# Fri3D_IRA_Power.net
KiCad netlist of a schematic drawn in Altium Designer
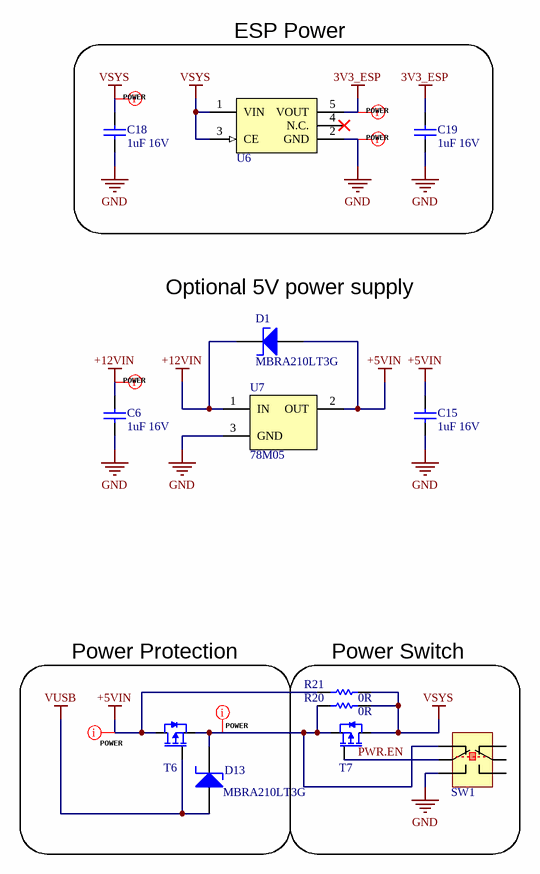
[diagram p0: Fri3D_IRA_Power.SchDoc]

(export (version "E")
  (design (tool "Eeschema 10.0.6"))
  (components
    (comp (ref "C6")
      (value "1uF 16V")
      (footprint "C0603_N")
      (description "Capacitor Ceramic")
      (fields (field (name "Comment") "CAP_CERAMIC"))
      (libsource (lib "Phyx_Components") (part "CAP_CERAMIC"))
    )
    (comp (ref "C15")
      (value "1uF 16V")
      (footprint "C0603_N")
      (description "Capacitor Ceramic")
      (fields (field (name "Comment") "CAP_CERAMIC"))
      (libsource (lib "Phyx_Components") (part "CAP_CERAMIC"))
    )
    (comp (ref "C18")
      (value "1uF 16V")
      (footprint "C0603_N")
      (description "Capacitor Ceramic")
      (fields (field (name "Comment") "CAP_CERAMIC"))
      (libsource (lib "Phyx_Components") (part "CAP_CERAMIC"))
    )
    (comp (ref "C19")
      (value "1uF 16V")
      (footprint "C0603_N")
      (description "Capacitor Ceramic")
      (fields (field (name "Comment") "CAP_CERAMIC"))
      (libsource (lib "Phyx_Components") (part "CAP_CERAMIC"))
    )
    (comp (ref "D1")
      (value "MBRA210LT3G")
      (footprint "SMA_AC")
      (description "=Description")
      (libsource (lib "Phyx_Components") (part "Schottky_AC"))
    )
    (comp (ref "D13")
      (value "MBRA210LT3G")
      (footprint "SMA_AC")
      (description "=Description")
      (libsource (lib "Phyx_Components") (part "Schottky_AC"))
    )
    (comp (ref "R20")
      (value "0R")
      (footprint "R0603_N")
      (fields (field (name "Comment") "RESISTOR"))
      (libsource (lib "Phyx_Components") (part "RESISTOR"))
    )
    (comp (ref "R21")
      (value "0R")
      (footprint "R0603_N")
      (fields (field (name "Comment") "RESISTOR"))
      (libsource (lib "Phyx_Components") (part "RESISTOR"))
    )
    (comp (ref "SW1")
      (value "Mini slide switch 2P2T")
      (footprint "MSS22D18")
      (libsource (lib "Phyx_Components") (part "SW_2P2T"))
    )
    (comp (ref "T6")
      (value "-2.3A -20V P-Ch MOSFET Vgs -1V")
      (footprint "SOT23-3")
      (description "=Description")
      (libsource (lib "Phyx_Components") (part "P_MOSFET_GSD"))
    )
    (comp (ref "T7")
      (value "-2.3A -20V P-Ch MOSFET Vgs -1V")
      (footprint "SOT23-3")
      (description "=Description")
      (libsource (lib "Phyx_Components") (part "P_MOSFET_GSD"))
    )
    (comp (ref "U6")
      (value "3V3 LDO 700mA 50mV")
      (footprint "SOT23-5")
      (description "=Designator")
      (libsource (lib "Phyx_Components") (part "XC6210_SOT"))
    )
    (comp (ref "U7")
      (value "78M05")
      (footprint "TO-252")
      (description "78M05 5V 750mA LDO")
      (libsource (lib "Phyx_Components") (part "78M05"))
    )
  )
  (nets
    (net (code "1") (name "+5VIN") (class "Default")
      (node (ref "C15") (pin "1") (pinfunction "1_1") (pintype "passive"))
      (node (ref "D1") (pin "A") (pinfunction "A_A") (pintype "passive"))
      (node (ref "R21") (pin "2") (pinfunction "2_2") (pintype "passive"))
      (node (ref "T6") (pin "3") (pinfunction "D_3") (pintype "passive"))
      (node (ref "U7") (pin "2") (pinfunction "OUT_2") (pintype "power_in"))
    )
    (net (code "2") (name "+12VIN") (class "Default")
      (node (ref "C6") (pin "1") (pinfunction "1_1") (pintype "passive"))
      (node (ref "D1") (pin "C") (pinfunction "C_C") (pintype "passive"))
      (node (ref "U7") (pin "1") (pinfunction "IN_1") (pintype "power_in"))
    )
    (net (code "3") (name "/PWR.EN") (class "Default")
      (node (ref "SW1") (pin "3") (pinfunction "3_3") (pintype "passive"))
      (node (ref "T7") (pin "1") (pinfunction "G_1") (pintype "passive"))
    )
    (net (code "4") (name "3V3_ESP") (class "Default")
      (node (ref "C19") (pin "1") (pinfunction "1_1") (pintype "passive"))
      (node (ref "U6") (pin "5") (pinfunction "VOUT_5") (pintype "power_in"))
    )
    (net (code "5") (name "GND") (class "Default")
      (node (ref "C15") (pin "2") (pinfunction "2_2") (pintype "passive"))
      (node (ref "C18") (pin "2") (pinfunction "2_2") (pintype "passive"))
      (node (ref "C19") (pin "2") (pinfunction "2_2") (pintype "passive"))
      (node (ref "C6") (pin "2") (pinfunction "2_2") (pintype "passive"))
      (node (ref "SW1") (pin "5") (pinfunction "5_5") (pintype "passive"))
      (node (ref "U6") (pin "2") (pinfunction "GND_2") (pintype "power_in"))
      (node (ref "U7") (pin "3") (pinfunction "GND_3") (pintype "power_in"))
    )
    (net (code "6") (name "Net-(T6-S)") (class "Default")
      (node (ref "D13") (pin "C") (pinfunction "C_C") (pintype "passive"))
      (node (ref "R20") (pin "2") (pinfunction "2_2") (pintype "passive"))
      (node (ref "SW1") (pin "1") (pinfunction "1_1") (pintype "passive"))
      (node (ref "T6") (pin "2") (pinfunction "S_2") (pintype "passive"))
      (node (ref "T7") (pin "2") (pinfunction "S_2") (pintype "passive"))
    )
    (net (code "7") (name "VSYS") (class "Default")
      (node (ref "C18") (pin "1") (pinfunction "1_1") (pintype "passive"))
      (node (ref "R20") (pin "1") (pinfunction "1_1") (pintype "passive"))
      (node (ref "R21") (pin "1") (pinfunction "1_1") (pintype "passive"))
      (node (ref "T7") (pin "3") (pinfunction "D_3") (pintype "passive"))
      (node (ref "U6") (pin "1") (pinfunction "VIN_1") (pintype "power_in"))
      (node (ref "U6") (pin "3") (pinfunction "CE_3") (pintype "input"))
    )
    (net (code "8") (name "VUSB") (class "Default")
      (node (ref "D13") (pin "A") (pinfunction "A_A") (pintype "passive"))
      (node (ref "T6") (pin "1") (pinfunction "G_1") (pintype "passive"))
    )
    (net (code "9") (name "unconnected-(SW1-5-Pad6)") (class "Default")
      (node (ref "SW1") (pin "6") (pinfunction "5_6") (pintype "passive"))
    )
    (net (code "10") (name "unconnected-(SW1-Pad2)") (class "Default")
      (node (ref "SW1") (pin "2") (pinfunction "2_2") (pintype "passive"))
    )
    (net (code "11") (name "unconnected-(SW1-Pad4)") (class "Default")
      (node (ref "SW1") (pin "4") (pinfunction "4_4") (pintype "passive"))
    )
    (net (code "12") (name "unconnected-(U6-N.C.-Pad4)") (class "Default")
      (node (ref "U6") (pin "4") (pinfunction "N.C._4") (pintype "passive+no_connect"))
    )
  )
)
